# Power.net
KiCad netlist of a schematic drawn in Altium Designer
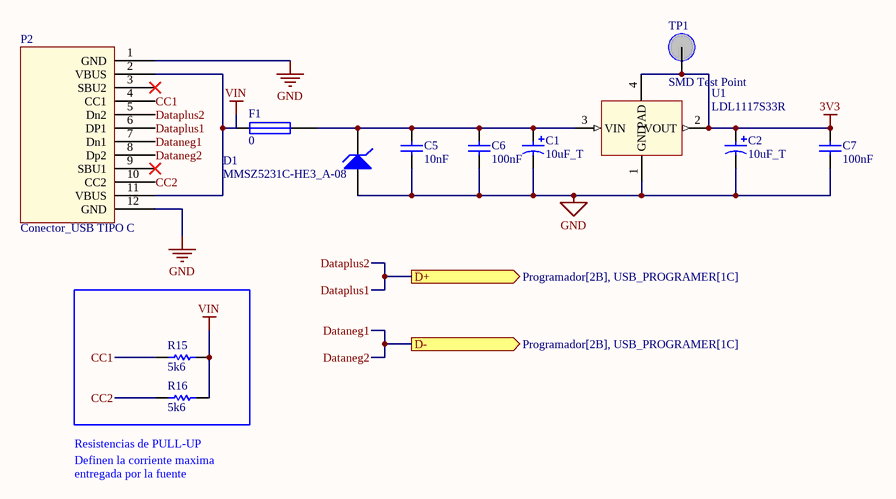
[diagram p0: Power.SchDoc]

(export (version "E")
  (design (tool "Eeschema 10.0.6"))
  (components
    (comp (ref "C1")
      (value "10uF_T")
      (footprint "C_0805_2013_c")
      (description "Capacitor SMD 0805 Tant")
      (fields
        (field (name "MANUFACTURER") "Vishay")
        (field (name "MANUFACTURER PART NUMBER") "TMCP1A106MTRF")
      )
      (libsource (lib "MyLibraryV2") (part "C_10uF_10V_b"))
    )
    (comp (ref "C2")
      (value "10uF_T")
      (footprint "C_0805_2013_c")
      (description "Capacitor SMD 0805 Tant")
      (fields
        (field (name "MANUFACTURER") "Vishay")
        (field (name "MANUFACTURER PART NUMBER") "TMCP1A106MTRF")
      )
      (libsource (lib "MyLibraryV2") (part "C_10uF_10V_b"))
    )
    (comp (ref "C5")
      (value "10nF")
      (footprint "C_0805_2013_b")
      (description "Capacitor SMD 0805")
      (fields (field (name "TOLERANCE") "5%") (field (name "MANUFACTURER") "KEMET"))
      (libsource (lib "MyLibraryV2") (part "C_10nF_50V_b"))
    )
    (comp (ref "C6")
      (value "100nF")
      (footprint "C_0805_2013_b")
      (description "Capacitor SMD 0805")
      (fields (field (name "TOLERANCE") "10%") (field (name "VOLTAGE") "50V"))
      (libsource (lib "MyLibraryV2") (part "C_100nF_50V_b"))
    )
    (comp (ref "C7")
      (value "100nF")
      (footprint "C_0805_2013_b")
      (description "Capacitor SMD 0805")
      (fields (field (name "TOLERANCE") "10%") (field (name "VOLTAGE") "50V"))
      (libsource (lib "MyLibraryV2") (part "C_100nF_50V_b"))
    )
    (comp (ref "D1")
      (value "MMSZ5231C-HE3_A-08")
      (footprint "D_SOD-123")
      (description "Diode SMD SOD-123 Zener 5V1")
      (fields (field (name "TOLERANCE") "2%") (field (name "MANUFACTURER") "Vishay Semiconductors"))
      (libsource (lib "Mi_lib") (part "D_MMSZ5231C-HE3_A-08"))
    )
    (comp (ref "F1")
      (value "0")
      (footprint "F_0805_2012")
      (description "(Generico) Fuse SMD 0805")
      (fields (field (name "PUBLISHER") "Altium Limited"))
      (libsource (lib "MyLibraryV2") (part "F_?_0805"))
    )
    (comp (ref "P2")
      (value "Conector_USB TIPO C")
      (footprint "P_USB_C")
      (description "Conector USB tip C basico")
      (libsource (lib "Mi_lib") (part "P_USB_C"))
    )
    (comp (ref "R15")
      (value "5k6")
      (footprint "R_0805_2012_a")
      (description "Resistor SMD 0805")
      (fields (field (name "TOLERANCE") "1%") (field (name "MANUFACTURER") "TE Connectivity"))
      (libsource (lib "MyLibraryV2") (part "R_5k6_b"))
    )
    (comp (ref "R16")
      (value "5k6")
      (footprint "R_0805_2012_a")
      (description "Resistor SMD 0805")
      (fields (field (name "TOLERANCE") "1%") (field (name "MANUFACTURER") "TE Connectivity"))
      (libsource (lib "MyLibraryV2") (part "R_5k6_b"))
    )
    (comp (ref "TP1")
      (value "SMD Test Point")
      (footprint "TP SMD")
      (description "Test Point SMD")
      (fields (field (name "PUBLISHER") "Altium Limited"))
      (libsource (lib "MyLibraryV2") (part "P_T_TP"))
    )
    (comp (ref "U1")
      (value "LDL1117S33R")
      (footprint "U_SOT-223")
      (description "LDL1117 Series 1.2 A 2.5 V High PSRR LDO Linear Voltage Regulator-SOT-223")
      (fields
        (field (name "MANUFACTURER") "STMicroelectronics")
        (field (name "MANUFACTURER PART NUMBER") "LDL1117S25R")
      )
      (libsource (lib "MyLibraryV2") (part "U_LDL1117"))
    )
  )
  (nets
    (net (code "1") (name "/CC1") (class "Default")
      (node (ref "P2") (pin "4") (pinfunction "CC1_4") (pintype "passive"))
      (node (ref "R15") (pin "2") (pinfunction "2_2") (pintype "passive"))
    )
    (net (code "2") (name "/CC2") (class "Default")
      (node (ref "P2") (pin "10") (pinfunction "CC2_10") (pintype "passive"))
      (node (ref "R16") (pin "1") (pinfunction "1_1") (pintype "passive"))
    )
    (net (code "3") (name "/Dataneg1") (class "Default")
      (node (ref "P2") (pin "7") (pinfunction "Dn1_7") (pintype "passive"))
      (node (ref "P2") (pin "8") (pinfunction "Dp2_8") (pintype "passive"))
    )
    (net (code "4") (name "/Dataplus1") (class "Default")
      (node (ref "P2") (pin "5") (pinfunction "Dn2_5") (pintype "passive"))
      (node (ref "P2") (pin "6") (pinfunction "DP1_6") (pintype "passive"))
    )
    (net (code "5") (name "3V3") (class "Default")
      (node (ref "C2") (pin "1") (pinfunction "1_1") (pintype "passive"))
      (node (ref "C7") (pin "2") (pinfunction "2_2") (pintype "passive"))
      (node (ref "TP1") (pin "1") (pinfunction "1_1") (pintype "passive"))
      (node (ref "U1") (pin "2") (pinfunction "VOUT_2") (pintype "output"))
      (node (ref "U1") (pin "4") (pinfunction "PAD_4") (pintype "passive"))
    )
    (net (code "6") (name "GND") (class "Default")
      (node (ref "C1") (pin "2") (pinfunction "2_2") (pintype "passive"))
      (node (ref "C2") (pin "2") (pinfunction "2_2") (pintype "passive"))
      (node (ref "C5") (pin "1") (pinfunction "1_1") (pintype "passive"))
      (node (ref "C6") (pin "1") (pinfunction "1_1") (pintype "passive"))
      (node (ref "C7") (pin "1") (pinfunction "1_1") (pintype "passive"))
      (node (ref "D1") (pin "2") (pinfunction "A_2") (pintype "passive"))
      (node (ref "P2") (pin "1") (pinfunction "GND_1") (pintype "passive"))
      (node (ref "P2") (pin "12") (pinfunction "GND_12") (pintype "passive"))
      (node (ref "U1") (pin "1") (pinfunction "GND_1") (pintype "power_in"))
    )
    (net (code "7") (name "Net-(D1-K)") (class "Default")
      (node (ref "C1") (pin "1") (pinfunction "1_1") (pintype "passive"))
      (node (ref "C5") (pin "2") (pinfunction "2_2") (pintype "passive"))
      (node (ref "C6") (pin "2") (pinfunction "2_2") (pintype "passive"))
      (node (ref "D1") (pin "1") (pinfunction "K_1") (pintype "passive"))
      (node (ref "F1") (pin "2") (pinfunction "2_2") (pintype "passive"))
      (node (ref "U1") (pin "3") (pinfunction "VIN_3") (pintype "input"))
    )
    (net (code "8") (name "VIN") (class "Default")
      (node (ref "F1") (pin "1") (pinfunction "1_1") (pintype "passive"))
      (node (ref "P2") (pin "11") (pinfunction "VBUS_11") (pintype "passive"))
      (node (ref "P2") (pin "2") (pinfunction "VBUS_2") (pintype "passive"))
      (node (ref "R15") (pin "1") (pinfunction "1_1") (pintype "passive"))
      (node (ref "R16") (pin "2") (pinfunction "2_2") (pintype "passive"))
    )
    (net (code "9") (name "unconnected-(P2-SBU1-Pad9)") (class "Default")
      (node (ref "P2") (pin "9") (pinfunction "SBU1_9") (pintype "passive+no_connect"))
    )
    (net (code "10") (name "unconnected-(P2-SBU2-Pad3)") (class "Default")
      (node (ref "P2") (pin "3") (pinfunction "SBU2_3") (pintype "passive+no_connect"))
    )
  )
)
